# T01_Synth_Glove_Prototype_Board_Amplifie.net
KiCad netlist of a schematic drawn in EAGLE
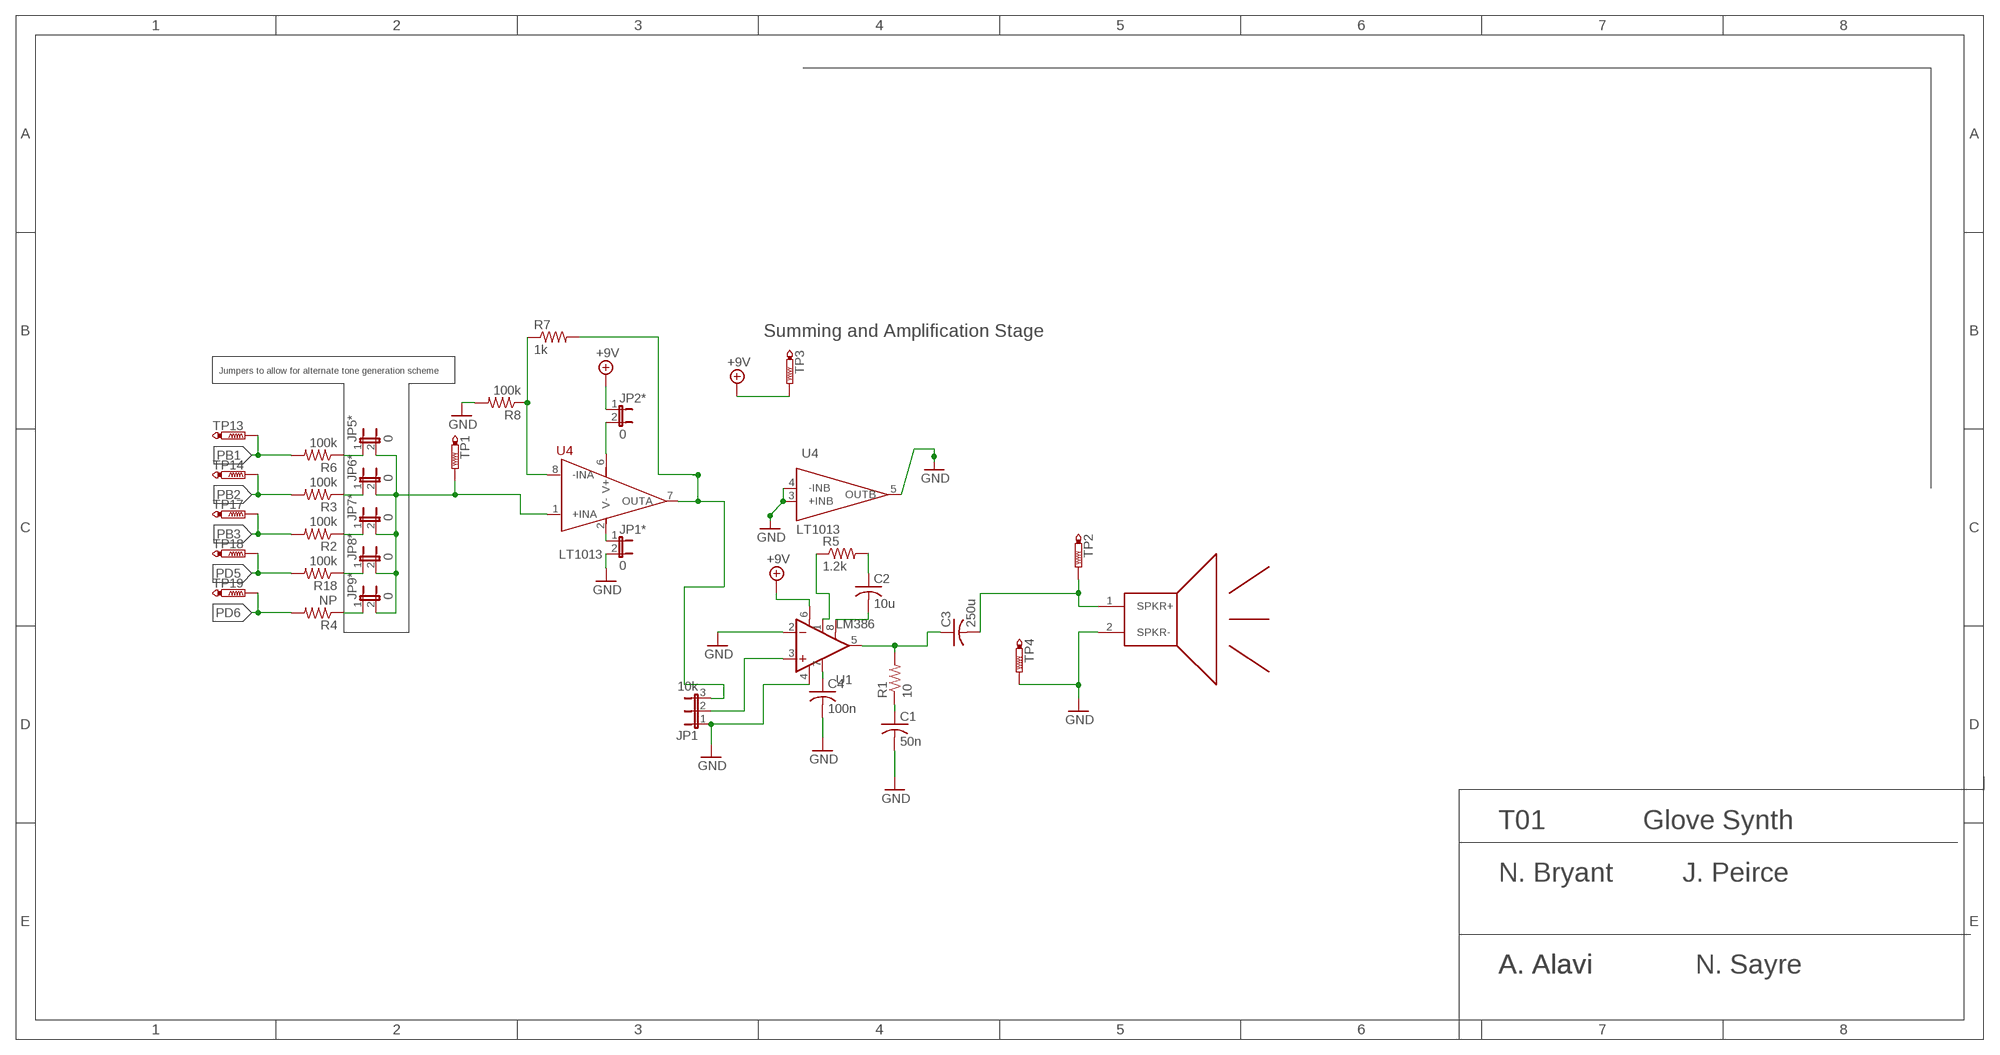
[diagram p0: schematic, sheet 1]

(export (version "E")
  (design (tool "Eeschema 10.0.6"))
  (components
    (comp (ref "C1")
      (value "50n")
      (footprint "eagle-import:C025-030X050")
      (libsource (lib "eagle-import") (part "C-US025-030X050"))
    )
    (comp (ref "C2")
      (value "10u")
      (footprint "eagle-import:C025-030X050")
      (libsource (lib "eagle-import") (part "C-US025-030X050"))
    )
    (comp (ref "C3")
      (value "250u")
      (footprint "eagle-import:C025-030X050")
      (libsource (lib "eagle-import") (part "C-US025-030X050"))
    )
    (comp (ref "C4")
      (value "100n")
      (footprint "eagle-import:C025-030X050")
      (libsource (lib "eagle-import") (part "C-US025-030X050"))
    )
    (comp (ref "JP1")
      (value "10k")
      (footprint "eagle-import:JP2")
      (libsource (lib "eagle-import") (part "JP2E"))
    )
    (comp (ref "JP1*")
      (value "0")
      (footprint "eagle-import:JP1")
      (libsource (lib "eagle-import") (part "JP1E"))
    )
    (comp (ref "JP2*")
      (value "0")
      (footprint "eagle-import:JP1")
      (libsource (lib "eagle-import") (part "JP1E"))
    )
    (comp (ref "JP5*")
      (value "0")
      (footprint "eagle-import:JP1")
      (libsource (lib "eagle-import") (part "JP1E"))
    )
    (comp (ref "JP6*")
      (value "0")
      (footprint "eagle-import:JP1")
      (libsource (lib "eagle-import") (part "JP1E"))
    )
    (comp (ref "JP7*")
      (value "0")
      (footprint "eagle-import:JP1")
      (libsource (lib "eagle-import") (part "JP1E"))
    )
    (comp (ref "JP8*")
      (value "0")
      (footprint "eagle-import:JP1")
      (libsource (lib "eagle-import") (part "JP1E"))
    )
    (comp (ref "JP9*")
      (value "0")
      (footprint "eagle-import:JP1")
      (libsource (lib "eagle-import") (part "JP1E"))
    )
    (comp (ref "R1")
      (value "10")
      (footprint "eagle-import:0204V")
      (libsource (lib "eagle-import") (part "R-US_0204/2V"))
    )
    (comp (ref "R2")
      (value "100k")
      (footprint "eagle-import:0603-RES")
      (libsource (lib "eagle-import") (part "RESISTOR0603"))
    )
    (comp (ref "R3")
      (value "100k")
      (footprint "eagle-import:0603-RES")
      (libsource (lib "eagle-import") (part "RESISTOR0603"))
    )
    (comp (ref "R4")
      (value "NP")
      (footprint "eagle-import:0603-RES")
      (libsource (lib "eagle-import") (part "RESISTOR0603"))
    )
    (comp (ref "R5")
      (value "1.2k")
      (footprint "eagle-import:0204V")
      (libsource (lib "eagle-import") (part "R-US_0204/2V"))
    )
    (comp (ref "R6")
      (value "100k")
      (footprint "eagle-import:0603-RES")
      (libsource (lib "eagle-import") (part "RESISTOR0603"))
    )
    (comp (ref "R7")
      (value "1k")
      (footprint "eagle-import:0603-RES")
      (libsource (lib "eagle-import") (part "RESISTOR0603"))
    )
    (comp (ref "R8")
      (value "100k")
      (footprint "eagle-import:0603-RES")
      (libsource (lib "eagle-import") (part "RESISTOR0603"))
    )
    (comp (ref "R18")
      (value "100k")
      (footprint "eagle-import:0603-RES")
      (libsource (lib "eagle-import") (part "RESISTOR0603"))
    )
    (comp (ref "TP1")
      (value "PTR1B2,54")
      (footprint "eagle-import:B2,54")
      (libsource (lib "eagle-import") (part "PTR1B2,54"))
    )
    (comp (ref "TP2")
      (value "PTR1B2,54")
      (footprint "eagle-import:B2,54")
      (libsource (lib "eagle-import") (part "PTR1B2,54"))
    )
    (comp (ref "TP3")
      (value "PTR1B2,54")
      (footprint "eagle-import:B2,54")
      (libsource (lib "eagle-import") (part "PTR1B2,54"))
    )
    (comp (ref "TP4")
      (value "PTR1B2,54")
      (footprint "eagle-import:B2,54")
      (libsource (lib "eagle-import") (part "PTR1B2,54"))
    )
    (comp (ref "TP13")
      (value "PTR1B2,54")
      (footprint "eagle-import:B2,54")
      (libsource (lib "eagle-import") (part "PTR1B2,54"))
    )
    (comp (ref "TP14")
      (value "PTR1B2,54")
      (footprint "eagle-import:B2,54")
      (libsource (lib "eagle-import") (part "PTR1B2,54"))
    )
    (comp (ref "TP17")
      (value "PTR1B2,54")
      (footprint "eagle-import:B2,54")
      (libsource (lib "eagle-import") (part "PTR1B2,54"))
    )
    (comp (ref "TP18")
      (value "PTR1B2,54")
      (footprint "eagle-import:B2,54")
      (libsource (lib "eagle-import") (part "PTR1B2,54"))
    )
    (comp (ref "TP19")
      (value "PTR1B2,54")
      (footprint "eagle-import:B2,54")
      (libsource (lib "eagle-import") (part "PTR1B2,54"))
    )
    (comp (ref "U$1")
      (value "SPEAKER")
      (footprint "eagle-import:JP1")
      (libsource (lib "eagle-import") (part "SPEAKER"))
    )
    (comp (ref "U1")
      (value "LM386")
      (footprint "eagle-import:DIP08")
      (libsource (lib "eagle-import") (part "LM386"))
    )
    (comp (ref "U4")
      (value "LT1013")
      (footprint "eagle-import:SO08")
      (libsource (lib "eagle-import") (part "LT1013"))
    )
  )
  (nets
    (net (code "1") (name "+9V") (class "Default")
      (node (ref "JP2*") (pin "1") (pinfunction "1_1") (pintype "passive"))
      (node (ref "TP3") (pin "TP") (pinfunction "TP_TP") (pintype "input"))
      (node (ref "U1") (pin "6") (pinfunction "V+_6") (pintype "power_in"))
    )
    (net (code "2") (name "GND") (class "Default")
      (node (ref "C1") (pin "2") (pinfunction "2_2") (pintype "passive"))
      (node (ref "C4") (pin "2") (pinfunction "2_2") (pintype "passive"))
      (node (ref "JP1") (pin "1") (pinfunction "1_1") (pintype "passive"))
      (node (ref "JP1*") (pin "2") (pinfunction "2_2") (pintype "passive"))
      (node (ref "R8") (pin "2") (pinfunction "2_2") (pintype "passive"))
      (node (ref "TP4") (pin "TP") (pinfunction "TP_TP") (pintype "input"))
      (node (ref "U$1") (pin "2") (pinfunction "SPKR-_2") (pintype "bidirectional"))
      (node (ref "U1") (pin "2") (pinfunction "-IN_2") (pintype "input"))
      (node (ref "U1") (pin "4") (pinfunction "V-_4") (pintype "power_in"))
      (node (ref "U4") (pin "3") (pinfunction "+INB_3") (pintype "bidirectional"))
      (node (ref "U4") (pin "4") (pinfunction "-INB_4") (pintype "bidirectional"))
      (node (ref "U4") (pin "5") (pinfunction "OUTB_5") (pintype "bidirectional"))
    )
    (net (code "3") (name "Net-(C1-Pad1)") (class "Default")
      (node (ref "C1") (pin "1") (pinfunction "1_1") (pintype "passive"))
      (node (ref "R1") (pin "1") (pinfunction "1_1") (pintype "passive"))
    )
    (net (code "4") (name "Net-(C2-Pad1)") (class "Default")
      (node (ref "C2") (pin "1") (pinfunction "1_1") (pintype "passive"))
      (node (ref "R5") (pin "2") (pinfunction "2_2") (pintype "passive"))
    )
    (net (code "5") (name "Net-(C2-Pad2)") (class "Default")
      (node (ref "C2") (pin "2") (pinfunction "2_2") (pintype "passive"))
      (node (ref "U1") (pin "8") (pinfunction "GAIN_8") (pintype "bidirectional"))
    )
    (net (code "6") (name "Net-(JP5*-Pad1)") (class "Default")
      (node (ref "JP5*") (pin "1") (pinfunction "1_1") (pintype "passive"))
      (node (ref "R6") (pin "1") (pinfunction "1_1") (pintype "passive"))
    )
    (net (code "7") (name "Net-(JP6*-Pad1)") (class "Default")
      (node (ref "JP6*") (pin "1") (pinfunction "1_1") (pintype "passive"))
      (node (ref "R3") (pin "1") (pinfunction "1_1") (pintype "passive"))
    )
    (net (code "8") (name "Net-(JP7*-Pad1)") (class "Default")
      (node (ref "JP7*") (pin "1") (pinfunction "1_1") (pintype "passive"))
      (node (ref "R2") (pin "1") (pinfunction "1_1") (pintype "passive"))
    )
    (net (code "9") (name "Net-(JP8*-Pad1)") (class "Default")
      (node (ref "JP8*") (pin "1") (pinfunction "1_1") (pintype "passive"))
      (node (ref "R18") (pin "1") (pinfunction "1_1") (pintype "passive"))
    )
    (net (code "10") (name "Net-(JP9*-Pad1)") (class "Default")
      (node (ref "JP9*") (pin "1") (pinfunction "1_1") (pintype "passive"))
      (node (ref "R4") (pin "1") (pinfunction "1_1") (pintype "passive"))
    )
    (net (code "11") (name "Net-(R5-Pad1)") (class "Default")
      (node (ref "R5") (pin "1") (pinfunction "1_1") (pintype "passive"))
      (node (ref "U1") (pin "1") (pinfunction "GAIN_1") (pintype "bidirectional"))
    )
    (net (code "12") (name "Net-(U$1-SPKR+)") (class "Default")
      (node (ref "C3") (pin "2") (pinfunction "2_2") (pintype "passive"))
      (node (ref "TP2") (pin "TP") (pinfunction "TP_TP") (pintype "input"))
      (node (ref "U$1") (pin "1") (pinfunction "SPKR+_1") (pintype "bidirectional"))
    )
    (net (code "13") (name "Net-(U1-+IN)") (class "Default")
      (node (ref "JP1") (pin "2") (pinfunction "2_2") (pintype "passive"))
      (node (ref "U1") (pin "3") (pinfunction "+IN_3") (pintype "input"))
    )
    (net (code "14") (name "Net-(U1-BP)") (class "Default")
      (node (ref "C4") (pin "1") (pinfunction "1_1") (pintype "passive"))
      (node (ref "U1") (pin "7") (pinfunction "BP_7") (pintype "bidirectional"))
    )
    (net (code "15") (name "Net-(U1-OUT)") (class "Default")
      (node (ref "C3") (pin "1") (pinfunction "1_1") (pintype "passive"))
      (node (ref "R1") (pin "2") (pinfunction "2_2") (pintype "passive"))
      (node (ref "U1") (pin "5") (pinfunction "OUT_5") (pintype "output"))
    )
    (net (code "16") (name "Net-(U4-+INA)") (class "Default")
      (node (ref "JP5*") (pin "2") (pinfunction "2_2") (pintype "passive"))
      (node (ref "JP6*") (pin "2") (pinfunction "2_2") (pintype "passive"))
      (node (ref "JP7*") (pin "2") (pinfunction "2_2") (pintype "passive"))
      (node (ref "JP8*") (pin "2") (pinfunction "2_2") (pintype "passive"))
      (node (ref "JP9*") (pin "2") (pinfunction "2_2") (pintype "passive"))
      (node (ref "TP1") (pin "TP") (pinfunction "TP_TP") (pintype "input"))
      (node (ref "U4") (pin "1") (pinfunction "+INA_1") (pintype "bidirectional"))
    )
    (net (code "17") (name "Net-(U4--INA)") (class "Default")
      (node (ref "R7") (pin "1") (pinfunction "1_1") (pintype "passive"))
      (node (ref "R8") (pin "1") (pinfunction "1_1") (pintype "passive"))
      (node (ref "U4") (pin "8") (pinfunction "-INA_8") (pintype "bidirectional"))
    )
    (net (code "18") (name "Net-(U4-OUTA)") (class "Default")
      (node (ref "JP1") (pin "3") (pinfunction "3_3") (pintype "passive"))
      (node (ref "R7") (pin "2") (pinfunction "2_2") (pintype "passive"))
      (node (ref "U4") (pin "7") (pinfunction "OUTA_7") (pintype "bidirectional"))
    )
    (net (code "19") (name "Net-(U4-V+)") (class "Default")
      (node (ref "JP2*") (pin "2") (pinfunction "2_2") (pintype "passive"))
      (node (ref "U4") (pin "6") (pinfunction "V+_6") (pintype "bidirectional"))
    )
    (net (code "20") (name "Net-(U4-V-)") (class "Default")
      (node (ref "JP1*") (pin "1") (pinfunction "1_1") (pintype "passive"))
      (node (ref "U4") (pin "2") (pinfunction "V-_2") (pintype "bidirectional"))
    )
    (net (code "21") (name "PB1") (class "Default")
      (node (ref "R6") (pin "2") (pinfunction "2_2") (pintype "passive"))
      (node (ref "TP13") (pin "TP") (pinfunction "TP_TP") (pintype "input"))
    )
    (net (code "22") (name "PB2") (class "Default")
      (node (ref "R3") (pin "2") (pinfunction "2_2") (pintype "passive"))
      (node (ref "TP14") (pin "TP") (pinfunction "TP_TP") (pintype "input"))
    )
    (net (code "23") (name "PB3") (class "Default")
      (node (ref "R2") (pin "2") (pinfunction "2_2") (pintype "passive"))
      (node (ref "TP17") (pin "TP") (pinfunction "TP_TP") (pintype "input"))
    )
    (net (code "24") (name "PD5") (class "Default")
      (node (ref "R18") (pin "2") (pinfunction "2_2") (pintype "passive"))
      (node (ref "TP18") (pin "TP") (pinfunction "TP_TP") (pintype "input"))
    )
    (net (code "25") (name "PD6") (class "Default")
      (node (ref "R4") (pin "2") (pinfunction "2_2") (pintype "passive"))
      (node (ref "TP19") (pin "TP") (pinfunction "TP_TP") (pintype "input"))
    )
  )
)
